# IMU.net
KiCad netlist of a schematic drawn in Altium Designer
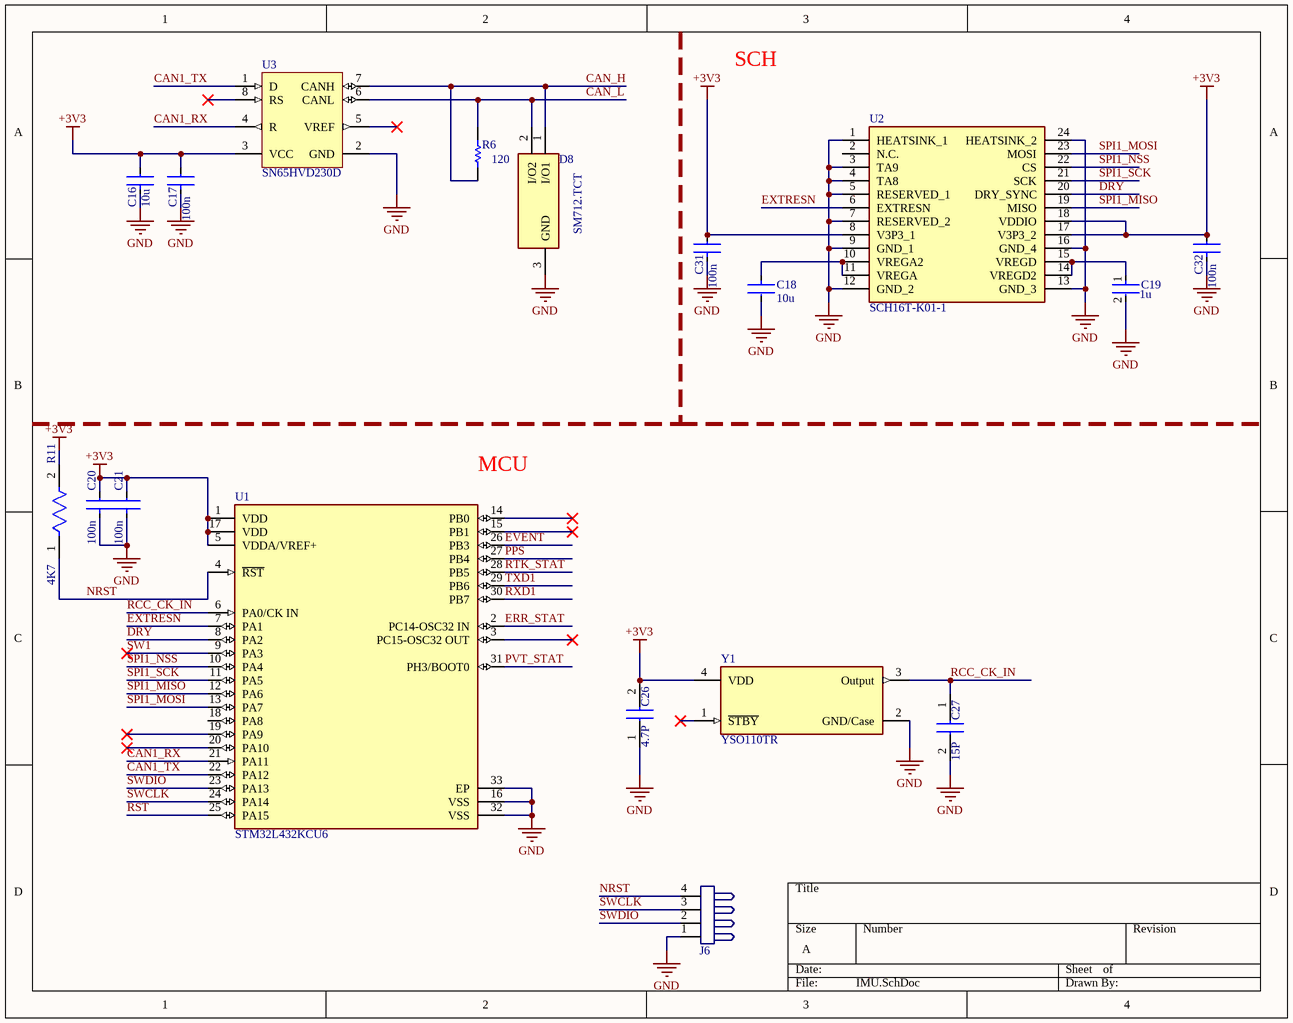
[diagram p0: IMU.SchDoc]

(export (version "E")
  (design (tool "Eeschema 10.0.6"))
  (components
    (comp (ref "C16")
      (value "10u")
      (footprint "FP-C1608-080-IPC_A")
      (description "CAP CER 10UF 25V X5R 0603")
      (fields (field (name "TOLERANCE") "20%") (field (name "Comment") "C1608X5R1E106M080AC"))
      (libsource (lib "Altium Content Vault") (part "11868f565c42a9108669ba33697ecf6"))
    )
    (comp (ref "C17")
      (value "100n")
      (footprint "FP-C1005-050-0_05-IPC_C")
      (description "Multilayer Ceramic Capacitors 100nF ±10% 50V X7R SMD 0402")
      (fields (field (name "VOLTAGE") "50V") (field (name "TOLERANCE") "10%"))
      (libsource (lib "Altium Content Vault") (part "b4654b650e69147ec39a6b967a45e02"))
    )
    (comp (ref "C18")
      (value "10u")
      (footprint "FP-C1608-080-IPC_A")
      (description "CAP CER 10UF 25V X5R 0603")
      (fields (field (name "TOLERANCE") "20%") (field (name "Comment") "C1608X5R1E106M080AC"))
      (libsource (lib "Altium Content Vault") (part "11868f565c42a9108669ba33697ecf6"))
    )
    (comp (ref "C19")
      (value "C1005X5R1V105K050BC")
      (footprint "FP-C1005-050-0_05-IPC_C")
      (description "Multilayer Ceramic Capacitors 1μF ±10% 35V X5R SMD 0402")
      (fields (field (name "CAPACITANCE") "1u") (field (name "TOLERANCE") "10%"))
      (libsource (lib "") (part "b4654b650e69147ec39a6b967a45e02_1"))
    )
    (comp (ref "C20")
      (value "100n")
      (footprint "FP-C1005-050-0_05-IPC_C")
      (description "Multilayer Ceramic Capacitors 100nF ±10% 50V X7R SMD 0402")
      (fields (field (name "VOLTAGE") "50V") (field (name "TOLERANCE") "10%"))
      (libsource (lib "Altium Content Vault") (part "b4654b650e69147ec39a6b967a45e02"))
    )
    (comp (ref "C21")
      (value "100n")
      (footprint "FP-C1005-050-0_05-IPC_C")
      (description "Multilayer Ceramic Capacitors 100nF ±10% 50V X7R SMD 0402")
      (fields (field (name "VOLTAGE") "50V") (field (name "TOLERANCE") "10%"))
      (libsource (lib "Altium Content Vault") (part "b4654b650e69147ec39a6b967a45e02"))
    )
    (comp (ref "C26")
      (value "4.7P")
      (footprint "SamacSys:CAPC1005X55N")
      (description "Capacitor")
      (fields
        (field (name "MANUFACTURER_PART_NUMBER") "CC0402BRNPO9BN4R7")
        (field (name "MOUSER PART NUMBER") "603-CC402BRNPO9BN4R7")
      )
      (libsource (lib "*") (part "CC0402BRNPO9BN4R7"))
    )
    (comp (ref "C27")
      (value "15P")
      (footprint "SamacSys:CAPC1005X55N")
      (description "Capacitor")
      (fields
        (field (name "MANUFACTURER_PART_NUMBER") "CC0402JRNPO8BN150")
        (field (name "MOUSER PART NUMBER") "603-CC402JRNPO8BN150")
      )
      (libsource (lib "*") (part "CC0402JRNPO8BN150"))
    )
    (comp (ref "C31")
      (value "100n")
      (footprint "FP-C1005-050-0_05-IPC_C")
      (description "Multilayer Ceramic Capacitors 100nF ±10% 50V X7R SMD 0402")
      (fields (field (name "VOLTAGE") "50V") (field (name "TOLERANCE") "10%"))
      (libsource (lib "Altium Content Vault") (part "b4654b650e69147ec39a6b967a45e02"))
    )
    (comp (ref "C32")
      (value "100n")
      (footprint "FP-C1005-050-0_05-IPC_C")
      (description "Multilayer Ceramic Capacitors 100nF ±10% 50V X7R SMD 0402")
      (fields (field (name "VOLTAGE") "50V") (field (name "TOLERANCE") "10%"))
      (libsource (lib "Altium Content Vault") (part "b4654b650e69147ec39a6b967a45e02"))
    )
    (comp (ref "D8")
      (value "SM712.TCT")
      (footprint "SamacSys:SOT95P237X112-3N")
      (description "Diode")
      (fields (field (name "MOUSER PART NUMBER") "947-SM712.TCT"))
      (libsource (lib "*") (part "SM712.TCT"))
    )
    (comp (ref "J6")
      (value "PHDR 4")
      (footprint "PHDR2X2")
      (description "PinHeader")
      (libsource (lib "ParsaLibrary") (part "PHDR 4"))
    )
    (comp (ref "R6")
      (value "120")
      (footprint "RESC1005X40X25NL05T10")
      (fields (field (name "MANUFACTURER") "Yageo / Phycomp") (field (name "PART NUMBER") "RC0402FR-07120RL"))
      (libsource (lib "Altium Content Vault") (part "RES"))
    )
    (comp (ref "R11")
      (value "4K7")
      (footprint "FP-RC0402-0_4-MFG")
      (fields (field (name "TOLERANCE") "5%") (field (name "Comment") "RC0402JR-074K7L"))
      (libsource (lib "Altium Content Vault") (part "RC0402JR-074K7L"))
    )
    (comp (ref "U1")
      (value "STM32L432KCU6")
      (footprint "FP-UFQFPN32-A0B8-MFG")
      (description "IC MCU 32BIT 256KB FLASH 32QFPN")
      (fields
        (field (name "OCTOPART") "https://octopart.com/stm32l432kcu6-stmicroelectronics-71093510")
        (field (name "MANUFACTURER") "STMicroelectronics")
      )
      (libsource (lib "Altium Content Vault") (part "f3240dca552e0aa49c1b4baba198c12"))
    )
    (comp (ref "U2")
      (value "SCH16T-K01-1")
      (footprint "SamacSys:SCH16TK011")
      (description "Undefined or Miscellaneous")
      (fields (field (name "MOUSER PART NUMBER") "81-SCH16T-K01-1"))
      (libsource (lib "*") (part "SCH16T-K01-1"))
    )
    (comp (ref "U3")
      (value "SN65HVD230D")
      (footprint "D0008A_M")
      (description "CAN Bus Transceiver, 3.3 V, -40 to 85 degC, 8-Pin SOIC (D), Green (RoHS & no Sb/Br), Tube")
      (fields (field (name "GENERIC PART NUMBER") "SN65HVD230"))
      (libsource (lib "Altium Content Vault") (part "TI-SN65HVD230D-SOIC_D-8"))
    )
    (comp (ref "Y1")
      (value "YSO110TR")
      (footprint "FP-ASE-MFG")
      (description "XTAL Oscillator 50MHz ±50ppm CMOS 3.3V 4-SMD 3.2mm x 2.5mm")
      (libsource (lib "Altium Content Vault") (part "61a724e6190563596ac712fef61ad37"))
    )
  )
  (nets
    (net (code "1") (name "+3V3") (class "Default")
      (node (ref "C16") (pin "2") (pinfunction "2_2") (pintype "passive"))
      (node (ref "C17") (pin "2") (pinfunction "2_2") (pintype "passive"))
      (node (ref "C20") (pin "2") (pinfunction "2_2") (pintype "passive"))
      (node (ref "C21") (pin "2") (pinfunction "2_2") (pintype "passive"))
      (node (ref "C26") (pin "2") (pinfunction "2_2") (pintype "passive"))
      (node (ref "C31") (pin "2") (pinfunction "2_2") (pintype "passive"))
      (node (ref "C32") (pin "2") (pinfunction "2_2") (pintype "passive"))
      (node (ref "R11") (pin "2") (pinfunction "2_2") (pintype "passive"))
      (node (ref "U1") (pin "1") (pinfunction "VDD_1") (pintype "power_in"))
      (node (ref "U1") (pin "17") (pinfunction "VDD_17") (pintype "power_in"))
      (node (ref "U1") (pin "5") (pinfunction "VDDA/VREF+_5") (pintype "power_in"))
      (node (ref "U2") (pin "17") (pinfunction "V3P3_2_17") (pintype "passive"))
      (node (ref "U2") (pin "18") (pinfunction "VDDIO_18") (pintype "passive"))
      (node (ref "U2") (pin "8") (pinfunction "V3P3_1_8") (pintype "passive"))
      (node (ref "U3") (pin "3") (pinfunction "VCC_3") (pintype "power_in"))
      (node (ref "Y1") (pin "4") (pinfunction "VDD_4") (pintype "power_in"))
    )
    (net (code "2") (name "/CAN1_RX") (class "Default")
      (node (ref "U1") (pin "21") (pinfunction "PA11_21") (pintype "input"))
      (node (ref "U3") (pin "4") (pinfunction "R_4") (pintype "output"))
    )
    (net (code "3") (name "/CAN1_TX") (class "Default")
      (node (ref "U1") (pin "22") (pinfunction "PA12_22") (pintype "bidirectional"))
      (node (ref "U3") (pin "1") (pinfunction "D_1") (pintype "input"))
    )
    (net (code "4") (name "/CAN_H") (class "Default")
      (node (ref "D8") (pin "1") (pinfunction "I/O1_1") (pintype "passive"))
      (node (ref "R6") (pin "1") (pinfunction "1_1") (pintype "passive"))
      (node (ref "U3") (pin "7") (pinfunction "CANH_7") (pintype "bidirectional"))
    )
    (net (code "5") (name "/CAN_L") (class "Default")
      (node (ref "D8") (pin "2") (pinfunction "I/O2_2") (pintype "passive"))
      (node (ref "R6") (pin "2") (pinfunction "2_2") (pintype "passive"))
      (node (ref "U3") (pin "6") (pinfunction "CANL_6") (pintype "bidirectional"))
    )
    (net (code "6") (name "/DRY") (class "Default")
      (node (ref "U1") (pin "8") (pinfunction "PA2_8") (pintype "bidirectional"))
      (node (ref "U2") (pin "20") (pinfunction "DRY_SYNC_20") (pintype "passive"))
    )
    (net (code "7") (name "/ERR_STAT") (class "Default")
      (node (ref "U1") (pin "2") (pinfunction "PC14-OSC32_IN_2") (pintype "bidirectional"))
    )
    (net (code "8") (name "/EVENT") (class "Default")
      (node (ref "U1") (pin "26") (pinfunction "PB3_26") (pintype "bidirectional"))
    )
    (net (code "9") (name "/EXTRESN") (class "Default")
      (node (ref "U1") (pin "7") (pinfunction "PA1_7") (pintype "bidirectional"))
      (node (ref "U2") (pin "6") (pinfunction "EXTRESN_6") (pintype "passive"))
    )
    (net (code "10") (name "/NRST") (class "Default")
      (node (ref "J6") (pin "4") (pinfunction "4_4") (pintype "passive"))
      (node (ref "R11") (pin "1") (pinfunction "1_1") (pintype "passive"))
      (node (ref "U1") (pin "4") (pinfunction "~{RST}_4") (pintype "input"))
    )
    (net (code "11") (name "/PPS") (class "Default")
      (node (ref "U1") (pin "27") (pinfunction "PB4_27") (pintype "bidirectional"))
    )
    (net (code "12") (name "/PVT_STAT") (class "Default")
      (node (ref "U1") (pin "31") (pinfunction "PH3/BOOT0_31") (pintype "bidirectional"))
    )
    (net (code "13") (name "/RCC_CK_IN") (class "Default")
      (node (ref "C27") (pin "1") (pinfunction "1_1") (pintype "passive"))
      (node (ref "U1") (pin "6") (pinfunction "PA0/CK_IN_6") (pintype "input"))
      (node (ref "Y1") (pin "3") (pinfunction "Output_3") (pintype "output"))
    )
    (net (code "14") (name "/RST") (class "Default")
      (node (ref "U1") (pin "25") (pinfunction "PA15_25") (pintype "bidirectional"))
    )
    (net (code "15") (name "/RTK_STAT") (class "Default")
      (node (ref "U1") (pin "28") (pinfunction "PB5_28") (pintype "bidirectional"))
    )
    (net (code "16") (name "/RXD1") (class "Default")
      (node (ref "U1") (pin "30") (pinfunction "PB7_30") (pintype "bidirectional"))
    )
    (net (code "17") (name "/SPI1_MISO") (class "Default")
      (node (ref "U1") (pin "12") (pinfunction "PA6_12") (pintype "bidirectional"))
      (node (ref "U2") (pin "19") (pinfunction "MISO_19") (pintype "passive"))
    )
    (net (code "18") (name "/SPI1_MOSI") (class "Default")
      (node (ref "U1") (pin "13") (pinfunction "PA7_13") (pintype "bidirectional"))
      (node (ref "U2") (pin "23") (pinfunction "MOSI_23") (pintype "passive"))
    )
    (net (code "19") (name "/SPI1_NSS") (class "Default")
      (node (ref "U1") (pin "10") (pinfunction "PA4_10") (pintype "bidirectional"))
      (node (ref "U2") (pin "22") (pinfunction "CS_22") (pintype "passive"))
    )
    (net (code "20") (name "/SPI1_SCK") (class "Default")
      (node (ref "U1") (pin "11") (pinfunction "PA5_11") (pintype "bidirectional"))
      (node (ref "U2") (pin "21") (pinfunction "SCK_21") (pintype "passive"))
    )
    (net (code "21") (name "/SW1") (class "Default")
      (node (ref "U1") (pin "9") (pinfunction "PA3_9") (pintype "bidirectional+no_connect"))
    )
    (net (code "22") (name "/SWCLK") (class "Default")
      (node (ref "J6") (pin "3") (pinfunction "3_3") (pintype "passive"))
      (node (ref "U1") (pin "24") (pinfunction "PA14_24") (pintype "bidirectional"))
    )
    (net (code "23") (name "/SWDIO") (class "Default")
      (node (ref "J6") (pin "2") (pinfunction "2_2") (pintype "passive"))
      (node (ref "U1") (pin "23") (pinfunction "PA13_23") (pintype "bidirectional"))
    )
    (net (code "24") (name "/TXD1") (class "Default")
      (node (ref "U1") (pin "29") (pinfunction "PB6_29") (pintype "bidirectional"))
    )
    (net (code "25") (name "GND") (class "Default")
      (node (ref "C16") (pin "1") (pinfunction "1_1") (pintype "passive"))
      (node (ref "C17") (pin "1") (pinfunction "1_1") (pintype "passive"))
      (node (ref "C18") (pin "2") (pinfunction "2_2") (pintype "passive"))
      (node (ref "C19") (pin "2") (pinfunction "2_2") (pintype "passive"))
      (node (ref "C20") (pin "1") (pinfunction "1_1") (pintype "passive"))
      (node (ref "C21") (pin "1") (pinfunction "1_1") (pintype "passive"))
      (node (ref "C26") (pin "1") (pinfunction "1_1") (pintype "passive"))
      (node (ref "C27") (pin "2") (pinfunction "2_2") (pintype "passive"))
      (node (ref "C31") (pin "1") (pinfunction "1_1") (pintype "passive"))
      (node (ref "C32") (pin "1") (pinfunction "1_1") (pintype "passive"))
      (node (ref "D8") (pin "3") (pinfunction "GND_3") (pintype "passive"))
      (node (ref "J6") (pin "1") (pinfunction "1_1") (pintype "passive"))
      (node (ref "U1") (pin "16") (pinfunction "VSS_16") (pintype "power_in"))
      (node (ref "U1") (pin "32") (pinfunction "VSS_32") (pintype "power_in"))
      (node (ref "U1") (pin "33") (pinfunction "EP_33") (pintype "power_in"))
      (node (ref "U2") (pin "1") (pinfunction "HEATSINK_1_1") (pintype "passive"))
      (node (ref "U2") (pin "12") (pinfunction "GND_2_12") (pintype "passive"))
      (node (ref "U2") (pin "13") (pinfunction "GND_3_13") (pintype "passive"))
      (node (ref "U2") (pin "16") (pinfunction "GND_4_16") (pintype "passive"))
      (node (ref "U2") (pin "24") (pinfunction "HEATSINK_2_24") (pintype "passive"))
      (node (ref "U2") (pin "3") (pinfunction "TA9_3") (pintype "passive"))
      (node (ref "U2") (pin "4") (pinfunction "TA8_4") (pintype "passive"))
      (node (ref "U2") (pin "5") (pinfunction "RESERVED_1_5") (pintype "passive"))
      (node (ref "U2") (pin "7") (pinfunction "RESERVED_2_7") (pintype "passive"))
      (node (ref "U2") (pin "9") (pinfunction "GND_1_9") (pintype "passive"))
      (node (ref "U3") (pin "2") (pinfunction "GND_2") (pintype "power_in"))
      (node (ref "Y1") (pin "2") (pinfunction "GND/Case_2") (pintype "power_in"))
    )
    (net (code "26") (name "Net-(U2-VREGA)") (class "Default")
      (node (ref "C18") (pin "1") (pinfunction "1_1") (pintype "passive"))
      (node (ref "U2") (pin "10") (pinfunction "VREGA2_10") (pintype "passive"))
      (node (ref "U2") (pin "11") (pinfunction "VREGA_11") (pintype "passive"))
    )
    (net (code "27") (name "Net-(U2-VREGD)") (class "Default")
      (node (ref "C19") (pin "1") (pinfunction "1_1") (pintype "passive"))
      (node (ref "U2") (pin "14") (pinfunction "VREGD2_14") (pintype "passive"))
      (node (ref "U2") (pin "15") (pinfunction "VREGD_15") (pintype "passive"))
    )
    (net (code "28") (name "unconnected-(U1-PA8-Pad18)") (class "Default")
      (node (ref "U1") (pin "18") (pinfunction "PA8_18") (pintype "bidirectional"))
    )
    (net (code "29") (name "unconnected-(U1-PA9-Pad19)") (class "Default")
      (node (ref "U1") (pin "19") (pinfunction "PA9_19") (pintype "bidirectional+no_connect"))
    )
    (net (code "30") (name "unconnected-(U1-PA10-Pad20)") (class "Default")
      (node (ref "U1") (pin "20") (pinfunction "PA10_20") (pintype "bidirectional+no_connect"))
    )
    (net (code "31") (name "unconnected-(U1-PB0-Pad14)") (class "Default")
      (node (ref "U1") (pin "14") (pinfunction "PB0_14") (pintype "bidirectional+no_connect"))
    )
    (net (code "32") (name "unconnected-(U1-PB1-Pad15)") (class "Default")
      (node (ref "U1") (pin "15") (pinfunction "PB1_15") (pintype "bidirectional+no_connect"))
    )
    (net (code "33") (name "unconnected-(U1-PC15-OSC32_OUT-Pad3)") (class "Default")
      (node (ref "U1") (pin "3") (pinfunction "PC15-OSC32_OUT_3") (pintype "bidirectional+no_connect"))
    )
    (net (code "34") (name "unconnected-(U2-N.C.-Pad2)") (class "Default")
      (node (ref "U2") (pin "2") (pinfunction "N.C._2") (pintype "passive"))
    )
    (net (code "35") (name "unconnected-(U3-RS-Pad8)") (class "Default")
      (node (ref "U3") (pin "8") (pinfunction "RS_8") (pintype "input+no_connect"))
    )
    (net (code "36") (name "unconnected-(U3-VREF-Pad5)") (class "Default")
      (node (ref "U3") (pin "5") (pinfunction "VREF_5") (pintype "output+no_connect"))
    )
    (net (code "37") (name "unconnected-(Y1-~{STBY}-Pad1)") (class "Default")
      (node (ref "Y1") (pin "1") (pinfunction "~{STBY}_1") (pintype "input+no_connect"))
    )
  )
)
